# ADK_MEGA_2560-REV3.net
KiCad netlist of a schematic drawn in EAGLE
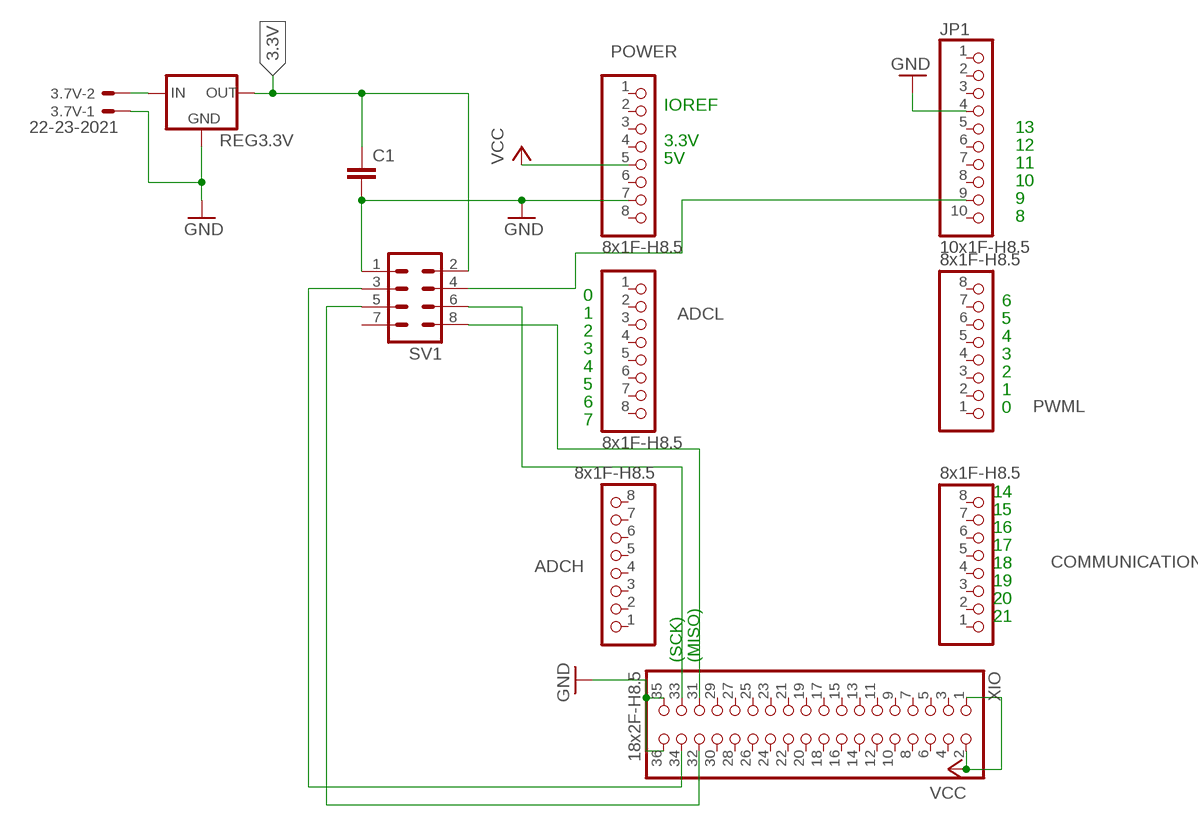
[diagram p0: schematic, sheet 1]

(export (version "E")
  (design (tool "Eeschema 10.0.6"))
  (components
    (comp (ref "3.7V")
      (value "22-23-2021")
      (footprint "eagle-import:22-23-2021")
      (fields (field (name "MF") "MOLEX"))
      (libsource (lib "eagle-import") (part "22-23-2021"))
    )
    (comp (ref "ADCH")
      (value "8x1F-H8.5")
      (footprint "eagle-import:1X08")
      (libsource (lib "eagle-import") (part "PINHD-1X8"))
    )
    (comp (ref "ADCL")
      (value "8x1F-H8.5")
      (footprint "eagle-import:1X08")
      (libsource (lib "eagle-import") (part "PINHD-1X8"))
    )
    (comp (ref "C1")
      (value "C-EU025-025X050")
      (footprint "eagle-import:C025-025X050")
      (libsource (lib "eagle-import") (part "C-EU025-025X050"))
    )
    (comp (ref "COMMUNICATION")
      (value "8x1F-H8.5")
      (footprint "eagle-import:1X08")
      (libsource (lib "eagle-import") (part "PINHD-1X8"))
    )
    (comp (ref "JP1")
      (value "10x1F-H8.5")
      (footprint "eagle-import:1X10")
      (libsource (lib "eagle-import") (part "PINHD-1X10"))
    )
    (comp (ref "POWER")
      (value "8x1F-H8.5")
      (footprint "eagle-import:1X08")
      (libsource (lib "eagle-import") (part "PINHD-1X8"))
    )
    (comp (ref "PWML")
      (value "8x1F-H8.5")
      (footprint "eagle-import:1X08")
      (libsource (lib "eagle-import") (part "PINHD-1X8"))
    )
    (comp (ref "REG3.3V")
      (value "78XXL")
      (footprint "eagle-import:78XXL")
      (libsource (lib "eagle-import") (part "78XXL"))
    )
    (comp (ref "SV1")
      (value "MA04-2")
      (footprint "eagle-import:MA04-2")
      (libsource (lib "eagle-import") (part "MA04-2"))
    )
    (comp (ref "XIO")
      (value "18x2F-H8.5")
      (footprint "eagle-import:2X18")
      (libsource (lib "eagle-import") (part "PINHD-2X18"))
    )
  )
  (nets
    (net (code "1") (name "3.3V") (class "Default")
      (node (ref "C1") (pin "1") (pinfunction "1_1") (pintype "passive"))
      (node (ref "REG3.3V") (pin "OUT") (pinfunction "OUT_OUT") (pintype "passive"))
      (node (ref "SV1") (pin "2") (pinfunction "2_2") (pintype "passive"))
    )
    (net (code "2") (name "GND") (class "Default")
      (node (ref "3.7V") (pin "1") (pinfunction "S_1") (pintype "passive"))
      (node (ref "C1") (pin "2") (pinfunction "2_2") (pintype "passive"))
      (node (ref "JP1") (pin "4") (pinfunction "4_4") (pintype "passive"))
      (node (ref "POWER") (pin "7") (pinfunction "7_7") (pintype "passive"))
      (node (ref "REG3.3V") (pin "GND") (pinfunction "GND_GND") (pintype "input"))
      (node (ref "SV1") (pin "1") (pinfunction "1_1") (pintype "passive"))
      (node (ref "XIO") (pin "35") (pinfunction "35_35") (pintype "passive"))
      (node (ref "XIO") (pin "36") (pinfunction "36_36") (pintype "passive"))
    )
    (net (code "3") (name "Net-(3.7VB-S)") (class "Default")
      (node (ref "3.7V") (pin "2") (pinfunction "S_2") (pintype "passive"))
      (node (ref "REG3.3V") (pin "IN") (pinfunction "IN_IN") (pintype "input"))
    )
    (net (code "4") (name "Net-(JP1-Pad9)") (class "Default")
      (node (ref "JP1") (pin "9") (pinfunction "9_9") (pintype "passive"))
      (node (ref "SV1") (pin "4") (pinfunction "4_4") (pintype "passive"))
    )
    (net (code "5") (name "Net-(SV1-Pad3)") (class "Default")
      (node (ref "SV1") (pin "3") (pinfunction "3_3") (pintype "passive"))
      (node (ref "XIO") (pin "34") (pinfunction "34_34") (pintype "passive"))
    )
    (net (code "6") (name "Net-(SV1-Pad5)") (class "Default")
      (node (ref "SV1") (pin "5") (pinfunction "5_5") (pintype "passive"))
      (node (ref "XIO") (pin "32") (pinfunction "32_32") (pintype "passive"))
    )
    (net (code "7") (name "Net-(SV1-Pad6)") (class "Default")
      (node (ref "SV1") (pin "6") (pinfunction "6_6") (pintype "passive"))
      (node (ref "XIO") (pin "33") (pinfunction "33_33") (pintype "passive"))
    )
    (net (code "8") (name "Net-(SV1-Pad8)") (class "Default")
      (node (ref "SV1") (pin "8") (pinfunction "8_8") (pintype "passive"))
      (node (ref "XIO") (pin "31") (pinfunction "31_31") (pintype "passive"))
    )
    (net (code "9") (name "VCC") (class "Default")
      (node (ref "POWER") (pin "5") (pinfunction "5_5") (pintype "passive"))
      (node (ref "XIO") (pin "1") (pinfunction "1_1") (pintype "passive"))
      (node (ref "XIO") (pin "2") (pinfunction "2_2") (pintype "passive"))
    )
    (net (code "10") (name "unconnected-(ADCH-Pad1)") (class "Default")
      (node (ref "ADCH") (pin "1") (pinfunction "1_1") (pintype "passive"))
    )
    (net (code "11") (name "unconnected-(ADCH-Pad2)") (class "Default")
      (node (ref "ADCH") (pin "2") (pinfunction "2_2") (pintype "passive"))
    )
    (net (code "12") (name "unconnected-(ADCH-Pad3)") (class "Default")
      (node (ref "ADCH") (pin "3") (pinfunction "3_3") (pintype "passive"))
    )
    (net (code "13") (name "unconnected-(ADCH-Pad4)") (class "Default")
      (node (ref "ADCH") (pin "4") (pinfunction "4_4") (pintype "passive"))
    )
    (net (code "14") (name "unconnected-(ADCH-Pad5)") (class "Default")
      (node (ref "ADCH") (pin "5") (pinfunction "5_5") (pintype "passive"))
    )
    (net (code "15") (name "unconnected-(ADCH-Pad6)") (class "Default")
      (node (ref "ADCH") (pin "6") (pinfunction "6_6") (pintype "passive"))
    )
    (net (code "16") (name "unconnected-(ADCH-Pad7)") (class "Default")
      (node (ref "ADCH") (pin "7") (pinfunction "7_7") (pintype "passive"))
    )
    (net (code "17") (name "unconnected-(ADCH-Pad8)") (class "Default")
      (node (ref "ADCH") (pin "8") (pinfunction "8_8") (pintype "passive"))
    )
    (net (code "18") (name "unconnected-(ADCL-Pad1)") (class "Default")
      (node (ref "ADCL") (pin "1") (pinfunction "1_1") (pintype "passive"))
    )
    (net (code "19") (name "unconnected-(ADCL-Pad2)") (class "Default")
      (node (ref "ADCL") (pin "2") (pinfunction "2_2") (pintype "passive"))
    )
    (net (code "20") (name "unconnected-(ADCL-Pad3)") (class "Default")
      (node (ref "ADCL") (pin "3") (pinfunction "3_3") (pintype "passive"))
    )
    (net (code "21") (name "unconnected-(ADCL-Pad4)") (class "Default")
      (node (ref "ADCL") (pin "4") (pinfunction "4_4") (pintype "passive"))
    )
    (net (code "22") (name "unconnected-(ADCL-Pad5)") (class "Default")
      (node (ref "ADCL") (pin "5") (pinfunction "5_5") (pintype "passive"))
    )
    (net (code "23") (name "unconnected-(ADCL-Pad6)") (class "Default")
      (node (ref "ADCL") (pin "6") (pinfunction "6_6") (pintype "passive"))
    )
    (net (code "24") (name "unconnected-(ADCL-Pad7)") (class "Default")
      (node (ref "ADCL") (pin "7") (pinfunction "7_7") (pintype "passive"))
    )
    (net (code "25") (name "unconnected-(ADCL-Pad8)") (class "Default")
      (node (ref "ADCL") (pin "8") (pinfunction "8_8") (pintype "passive"))
    )
    (net (code "26") (name "unconnected-(COMMUNICATION-Pad1)") (class "Default")
      (node (ref "COMMUNICATION") (pin "1") (pinfunction "1_1") (pintype "passive"))
    )
    (net (code "27") (name "unconnected-(COMMUNICATION-Pad2)") (class "Default")
      (node (ref "COMMUNICATION") (pin "2") (pinfunction "2_2") (pintype "passive"))
    )
    (net (code "28") (name "unconnected-(COMMUNICATION-Pad3)") (class "Default")
      (node (ref "COMMUNICATION") (pin "3") (pinfunction "3_3") (pintype "passive"))
    )
    (net (code "29") (name "unconnected-(COMMUNICATION-Pad4)") (class "Default")
      (node (ref "COMMUNICATION") (pin "4") (pinfunction "4_4") (pintype "passive"))
    )
    (net (code "30") (name "unconnected-(COMMUNICATION-Pad5)") (class "Default")
      (node (ref "COMMUNICATION") (pin "5") (pinfunction "5_5") (pintype "passive"))
    )
    (net (code "31") (name "unconnected-(COMMUNICATION-Pad6)") (class "Default")
      (node (ref "COMMUNICATION") (pin "6") (pinfunction "6_6") (pintype "passive"))
    )
    (net (code "32") (name "unconnected-(COMMUNICATION-Pad7)") (class "Default")
      (node (ref "COMMUNICATION") (pin "7") (pinfunction "7_7") (pintype "passive"))
    )
    (net (code "33") (name "unconnected-(COMMUNICATION-Pad8)") (class "Default")
      (node (ref "COMMUNICATION") (pin "8") (pinfunction "8_8") (pintype "passive"))
    )
    (net (code "34") (name "unconnected-(JP1-Pad1)") (class "Default")
      (node (ref "JP1") (pin "1") (pinfunction "1_1") (pintype "passive"))
    )
    (net (code "35") (name "unconnected-(JP1-Pad2)") (class "Default")
      (node (ref "JP1") (pin "2") (pinfunction "2_2") (pintype "passive"))
    )
    (net (code "36") (name "unconnected-(JP1-Pad3)") (class "Default")
      (node (ref "JP1") (pin "3") (pinfunction "3_3") (pintype "passive"))
    )
    (net (code "37") (name "unconnected-(JP1-Pad5)") (class "Default")
      (node (ref "JP1") (pin "5") (pinfunction "5_5") (pintype "passive"))
    )
    (net (code "38") (name "unconnected-(JP1-Pad6)") (class "Default")
      (node (ref "JP1") (pin "6") (pinfunction "6_6") (pintype "passive"))
    )
    (net (code "39") (name "unconnected-(JP1-Pad7)") (class "Default")
      (node (ref "JP1") (pin "7") (pinfunction "7_7") (pintype "passive"))
    )
    (net (code "40") (name "unconnected-(JP1-Pad8)") (class "Default")
      (node (ref "JP1") (pin "8") (pinfunction "8_8") (pintype "passive"))
    )
    (net (code "41") (name "unconnected-(JP1-Pad10)") (class "Default")
      (node (ref "JP1") (pin "10") (pinfunction "10_10") (pintype "passive"))
    )
    (net (code "42") (name "unconnected-(POWER-Pad1)") (class "Default")
      (node (ref "POWER") (pin "1") (pinfunction "1_1") (pintype "passive"))
    )
    (net (code "43") (name "unconnected-(POWER-Pad2)") (class "Default")
      (node (ref "POWER") (pin "2") (pinfunction "2_2") (pintype "passive"))
    )
    (net (code "44") (name "unconnected-(POWER-Pad3)") (class "Default")
      (node (ref "POWER") (pin "3") (pinfunction "3_3") (pintype "passive"))
    )
    (net (code "45") (name "unconnected-(POWER-Pad4)") (class "Default")
      (node (ref "POWER") (pin "4") (pinfunction "4_4") (pintype "passive"))
    )
    (net (code "46") (name "unconnected-(POWER-Pad6)") (class "Default")
      (node (ref "POWER") (pin "6") (pinfunction "6_6") (pintype "passive"))
    )
    (net (code "47") (name "unconnected-(POWER-Pad8)") (class "Default")
      (node (ref "POWER") (pin "8") (pinfunction "8_8") (pintype "passive"))
    )
    (net (code "48") (name "unconnected-(PWML-Pad1)") (class "Default")
      (node (ref "PWML") (pin "1") (pinfunction "1_1") (pintype "passive"))
    )
    (net (code "49") (name "unconnected-(PWML-Pad2)") (class "Default")
      (node (ref "PWML") (pin "2") (pinfunction "2_2") (pintype "passive"))
    )
    (net (code "50") (name "unconnected-(PWML-Pad3)") (class "Default")
      (node (ref "PWML") (pin "3") (pinfunction "3_3") (pintype "passive"))
    )
    (net (code "51") (name "unconnected-(PWML-Pad4)") (class "Default")
      (node (ref "PWML") (pin "4") (pinfunction "4_4") (pintype "passive"))
    )
    (net (code "52") (name "unconnected-(PWML-Pad5)") (class "Default")
      (node (ref "PWML") (pin "5") (pinfunction "5_5") (pintype "passive"))
    )
    (net (code "53") (name "unconnected-(PWML-Pad6)") (class "Default")
      (node (ref "PWML") (pin "6") (pinfunction "6_6") (pintype "passive"))
    )
    (net (code "54") (name "unconnected-(PWML-Pad7)") (class "Default")
      (node (ref "PWML") (pin "7") (pinfunction "7_7") (pintype "passive"))
    )
    (net (code "55") (name "unconnected-(PWML-Pad8)") (class "Default")
      (node (ref "PWML") (pin "8") (pinfunction "8_8") (pintype "passive"))
    )
    (net (code "56") (name "unconnected-(SV1-Pad7)") (class "Default")
      (node (ref "SV1") (pin "7") (pinfunction "7_7") (pintype "passive"))
    )
    (net (code "57") (name "unconnected-(XIO-Pad3)") (class "Default")
      (node (ref "XIO") (pin "3") (pinfunction "3_3") (pintype "passive"))
    )
    (net (code "58") (name "unconnected-(XIO-Pad4)") (class "Default")
      (node (ref "XIO") (pin "4") (pinfunction "4_4") (pintype "passive"))
    )
    (net (code "59") (name "unconnected-(XIO-Pad5)") (class "Default")
      (node (ref "XIO") (pin "5") (pinfunction "5_5") (pintype "passive"))
    )
    (net (code "60") (name "unconnected-(XIO-Pad6)") (class "Default")
      (node (ref "XIO") (pin "6") (pinfunction "6_6") (pintype "passive"))
    )
    (net (code "61") (name "unconnected-(XIO-Pad7)") (class "Default")
      (node (ref "XIO") (pin "7") (pinfunction "7_7") (pintype "passive"))
    )
    (net (code "62") (name "unconnected-(XIO-Pad8)") (class "Default")
      (node (ref "XIO") (pin "8") (pinfunction "8_8") (pintype "passive"))
    )
    (net (code "63") (name "unconnected-(XIO-Pad9)") (class "Default")
      (node (ref "XIO") (pin "9") (pinfunction "9_9") (pintype "passive"))
    )
    (net (code "64") (name "unconnected-(XIO-Pad10)") (class "Default")
      (node (ref "XIO") (pin "10") (pinfunction "10_10") (pintype "passive"))
    )
    (net (code "65") (name "unconnected-(XIO-Pad11)") (class "Default")
      (node (ref "XIO") (pin "11") (pinfunction "11_11") (pintype "passive"))
    )
    (net (code "66") (name "unconnected-(XIO-Pad12)") (class "Default")
      (node (ref "XIO") (pin "12") (pinfunction "12_12") (pintype "passive"))
    )
    (net (code "67") (name "unconnected-(XIO-Pad13)") (class "Default")
      (node (ref "XIO") (pin "13") (pinfunction "13_13") (pintype "passive"))
    )
    (net (code "68") (name "unconnected-(XIO-Pad14)") (class "Default")
      (node (ref "XIO") (pin "14") (pinfunction "14_14") (pintype "passive"))
    )
    (net (code "69") (name "unconnected-(XIO-Pad15)") (class "Default")
      (node (ref "XIO") (pin "15") (pinfunction "15_15") (pintype "passive"))
    )
    (net (code "70") (name "unconnected-(XIO-Pad16)") (class "Default")
      (node (ref "XIO") (pin "16") (pinfunction "16_16") (pintype "passive"))
    )
    (net (code "71") (name "unconnected-(XIO-Pad17)") (class "Default")
      (node (ref "XIO") (pin "17") (pinfunction "17_17") (pintype "passive"))
    )
    (net (code "72") (name "unconnected-(XIO-Pad18)") (class "Default")
      (node (ref "XIO") (pin "18") (pinfunction "18_18") (pintype "passive"))
    )
    (net (code "73") (name "unconnected-(XIO-Pad19)") (class "Default")
      (node (ref "XIO") (pin "19") (pinfunction "19_19") (pintype "passive"))
    )
    (net (code "74") (name "unconnected-(XIO-Pad20)") (class "Default")
      (node (ref "XIO") (pin "20") (pinfunction "20_20") (pintype "passive"))
    )
    (net (code "75") (name "unconnected-(XIO-Pad21)") (class "Default")
      (node (ref "XIO") (pin "21") (pinfunction "21_21") (pintype "passive"))
    )
    (net (code "76") (name "unconnected-(XIO-Pad22)") (class "Default")
      (node (ref "XIO") (pin "22") (pinfunction "22_22") (pintype "passive"))
    )
    (net (code "77") (name "unconnected-(XIO-Pad23)") (class "Default")
      (node (ref "XIO") (pin "23") (pinfunction "23_23") (pintype "passive"))
    )
    (net (code "78") (name "unconnected-(XIO-Pad24)") (class "Default")
      (node (ref "XIO") (pin "24") (pinfunction "24_24") (pintype "passive"))
    )
    (net (code "79") (name "unconnected-(XIO-Pad25)") (class "Default")
      (node (ref "XIO") (pin "25") (pinfunction "25_25") (pintype "passive"))
    )
    (net (code "80") (name "unconnected-(XIO-Pad26)") (class "Default")
      (node (ref "XIO") (pin "26") (pinfunction "26_26") (pintype "passive"))
    )
    (net (code "81") (name "unconnected-(XIO-Pad27)") (class "Default")
      (node (ref "XIO") (pin "27") (pinfunction "27_27") (pintype "passive"))
    )
    (net (code "82") (name "unconnected-(XIO-Pad28)") (class "Default")
      (node (ref "XIO") (pin "28") (pinfunction "28_28") (pintype "passive"))
    )
    (net (code "83") (name "unconnected-(XIO-Pad29)") (class "Default")
      (node (ref "XIO") (pin "29") (pinfunction "29_29") (pintype "passive"))
    )
    (net (code "84") (name "unconnected-(XIO-Pad30)") (class "Default")
      (node (ref "XIO") (pin "30") (pinfunction "30_30") (pintype "passive"))
    )
  )
)
